# Control.net
KiCad netlist of a schematic drawn in Altium Designer
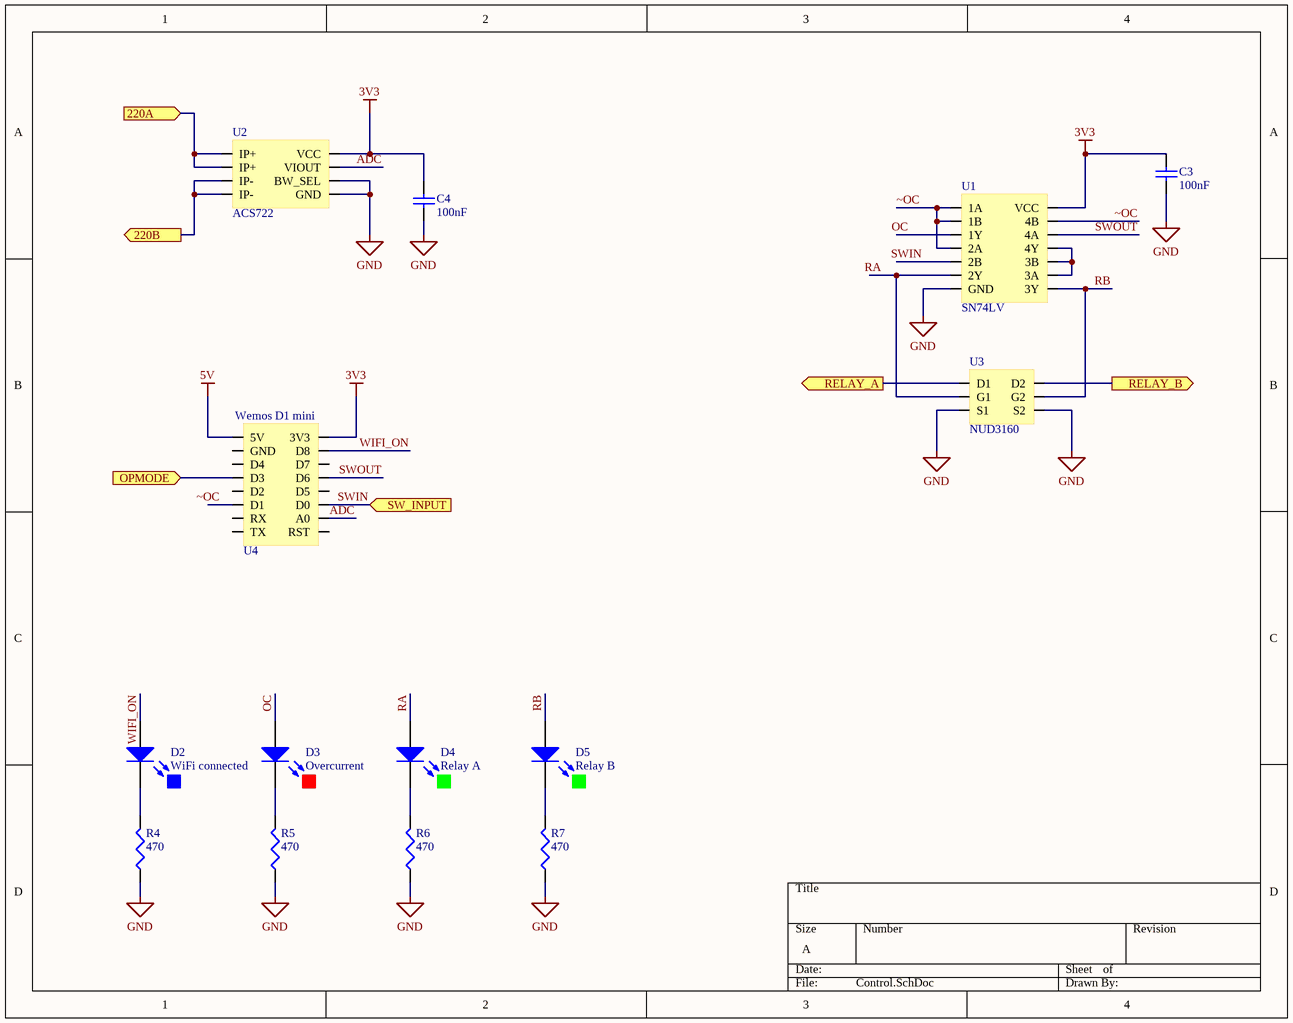
[diagram p0: Control.SchDoc]

(export (version "E")
  (design (tool "Eeschema 10.0.6"))
  (components
    (comp (ref "C3")
      (value "100nF")
      (footprint "C0805")
      (description "Capacitor")
      (fields
        (field (name "TOLERANCE") "80%")
        (field (name "VOLTAGE") "50V")
        (field (name "PUBLISHER") "Altium Limited")
      )
      (libsource (lib "Miscellaneous Devices") (part "Cap"))
    )
    (comp (ref "C4")
      (value "100nF")
      (footprint "C0805")
      (description "Capacitor")
      (fields
        (field (name "TOLERANCE") "80%")
        (field (name "VOLTAGE") "50V")
        (field (name "PUBLISHER") "Altium Limited")
      )
      (libsource (lib "Miscellaneous Devices") (part "Cap"))
    )
    (comp (ref "D2")
      (value "WiFi connected")
      (footprint "3.2X1.6X1.1")
      (description "Typical RED, GREEN, YELLOW, AMBER GaAs LED")
      (fields (field (name "PUBLISHER") "Altium Limited"))
      (libsource (lib "Miscellaneous Devices") (part "LED2"))
    )
    (comp (ref "D3")
      (value "Overcurrent")
      (footprint "3.2X1.6X1.1")
      (description "Typical RED, GREEN, YELLOW, AMBER GaAs LED")
      (fields (field (name "PUBLISHER") "Altium Limited"))
      (libsource (lib "Miscellaneous Devices") (part "LED2"))
    )
    (comp (ref "D4")
      (value "Relay A")
      (footprint "3.2X1.6X1.1")
      (description "Typical RED, GREEN, YELLOW, AMBER GaAs LED")
      (fields (field (name "PUBLISHER") "Altium Limited"))
      (libsource (lib "Miscellaneous Devices") (part "LED2"))
    )
    (comp (ref "D5")
      (value "Relay B")
      (footprint "3.2X1.6X1.1")
      (description "Typical RED, GREEN, YELLOW, AMBER GaAs LED")
      (fields (field (name "PUBLISHER") "Altium Limited"))
      (libsource (lib "Miscellaneous Devices") (part "LED2"))
    )
    (comp (ref "R4")
      (value "470")
      (footprint "J1-0603")
      (description "Resistor")
      (fields
        (field (name "TOLERANCE") "5%")
        (field (name "Comment") "Res3")
        (field (name "PUBLISHER") "Altium Limited")
      )
      (libsource (lib "Miscellaneous Devices") (part "Res3"))
    )
    (comp (ref "R5")
      (value "470")
      (footprint "J1-0603")
      (description "Resistor")
      (fields
        (field (name "TOLERANCE") "5%")
        (field (name "Comment") "Res3")
        (field (name "PUBLISHER") "Altium Limited")
      )
      (libsource (lib "Miscellaneous Devices") (part "Res3"))
    )
    (comp (ref "R6")
      (value "470")
      (footprint "J1-0603")
      (description "Resistor")
      (fields
        (field (name "TOLERANCE") "5%")
        (field (name "Comment") "Res3")
        (field (name "PUBLISHER") "Altium Limited")
      )
      (libsource (lib "Miscellaneous Devices") (part "Res3"))
    )
    (comp (ref "R7")
      (value "470")
      (footprint "J1-0603")
      (description "Resistor")
      (fields
        (field (name "TOLERANCE") "5%")
        (field (name "Comment") "Res3")
        (field (name "PUBLISHER") "Altium Limited")
      )
      (libsource (lib "Miscellaneous Devices") (part "Res3"))
    )
    (comp (ref "U1")
      (value "SN74LV")
      (footprint "TSSOP14")
      (description "IC GATE NAND 4CH 2-INP 14-SSOP")
      (libsource (lib "SmartplugComponents") (part "SN74LVC00APWR"))
    )
    (comp (ref "U2")
      (value "ACS722")
      (footprint "SOIC8")
      (description "SENSOR CURRENT HALL 20A AC/DC")
      (libsource (lib "SmartplugComponents") (part "ACS722LLCTR-20AB-T"))
    )
    (comp (ref "U3")
      (value "NUD3160")
      (footprint "SC-74")
      (description "IC INDCT LOAD DRVR INDUST SC74-6")
      (libsource (lib "SmartplugComponents") (part "NUD3160DMT1G"))
    )
    (comp (ref "U4")
      (value "Wemos D1 mini")
      (footprint "WEMOS_D1")
      (description "ESP8266 based MCU with Wi-Fi")
      (libsource (lib "SmartplugComponents") (part "ESP8266"))
    )
  )
  (nets
    (net (code "1") (name "/220A") (class "Default")
      (node (ref "U2") (pin "1") (pinfunction "IP+_1") (pintype "passive"))
      (node (ref "U2") (pin "2") (pinfunction "IP+_2") (pintype "passive"))
    )
    (net (code "2") (name "/220B") (class "Default")
      (node (ref "U2") (pin "3") (pinfunction "IP-_3") (pintype "passive"))
      (node (ref "U2") (pin "4") (pinfunction "IP-_4") (pintype "passive"))
    )
    (net (code "3") (name "/ADC") (class "Default")
      (node (ref "U2") (pin "7") (pinfunction "VIOUT_7") (pintype "passive"))
      (node (ref "U4") (pin "10") (pinfunction "A0_10") (pintype "passive"))
    )
    (net (code "4") (name "/OC") (class "Default")
      (node (ref "D3") (pin "1") (pinfunction "A_1") (pintype "passive"))
      (node (ref "U1") (pin "3") (pinfunction "1Y_3") (pintype "passive"))
    )
    (net (code "5") (name "/OPMODE") (class "Default")
      (node (ref "U4") (pin "4") (pinfunction "D3_4") (pintype "passive"))
    )
    (net (code "6") (name "/RA") (class "Default")
      (node (ref "D4") (pin "1") (pinfunction "A_1") (pintype "passive"))
      (node (ref "U1") (pin "6") (pinfunction "2Y_6") (pintype "passive"))
      (node (ref "U3") (pin "2") (pinfunction "G1_2") (pintype "passive"))
    )
    (net (code "7") (name "/RB") (class "Default")
      (node (ref "D5") (pin "1") (pinfunction "A_1") (pintype "passive"))
      (node (ref "U1") (pin "8") (pinfunction "3Y_8") (pintype "passive"))
      (node (ref "U3") (pin "5") (pinfunction "G2_5") (pintype "passive"))
    )
    (net (code "8") (name "/RELAY_A") (class "Default")
      (node (ref "U3") (pin "6") (pinfunction "D1_6") (pintype "passive"))
    )
    (net (code "9") (name "/RELAY_B") (class "Default")
      (node (ref "U3") (pin "3") (pinfunction "D2_3") (pintype "passive"))
    )
    (net (code "10") (name "/SWIN") (class "Default")
      (node (ref "U1") (pin "5") (pinfunction "2B_5") (pintype "passive"))
      (node (ref "U4") (pin "11") (pinfunction "D0_11") (pintype "passive"))
    )
    (net (code "11") (name "/SWOUT") (class "Default")
      (node (ref "U1") (pin "12") (pinfunction "4A_12") (pintype "passive"))
      (node (ref "U4") (pin "13") (pinfunction "D6_13") (pintype "passive"))
    )
    (net (code "12") (name "/WIFI_ON") (class "Default")
      (node (ref "D2") (pin "1") (pinfunction "A_1") (pintype "passive"))
      (node (ref "U4") (pin "15") (pinfunction "D8_15") (pintype "passive"))
    )
    (net (code "13") (name "/~OC") (class "Default")
      (node (ref "U1") (pin "1") (pinfunction "1A_1") (pintype "passive"))
      (node (ref "U1") (pin "13") (pinfunction "4B_13") (pintype "passive"))
      (node (ref "U1") (pin "2") (pinfunction "1B_2") (pintype "passive"))
      (node (ref "U1") (pin "4") (pinfunction "2A_4") (pintype "passive"))
      (node (ref "U4") (pin "6") (pinfunction "D1_6") (pintype "passive"))
    )
    (net (code "14") (name "3V3") (class "Default")
      (node (ref "C3") (pin "2") (pinfunction "2_2") (pintype "passive"))
      (node (ref "C4") (pin "2") (pinfunction "2_2") (pintype "passive"))
      (node (ref "U1") (pin "14") (pinfunction "VCC_14") (pintype "passive"))
      (node (ref "U2") (pin "8") (pinfunction "VCC_8") (pintype "passive"))
      (node (ref "U4") (pin "16") (pinfunction "3V3_16") (pintype "passive"))
    )
    (net (code "15") (name "5V") (class "Default")
      (node (ref "U4") (pin "1") (pinfunction "5V_1") (pintype "passive"))
    )
    (net (code "16") (name "GND") (class "Default")
      (node (ref "C3") (pin "1") (pinfunction "1_1") (pintype "passive"))
      (node (ref "C4") (pin "1") (pinfunction "1_1") (pintype "passive"))
      (node (ref "R4") (pin "1") (pinfunction "1_1") (pintype "passive"))
      (node (ref "R5") (pin "1") (pinfunction "1_1") (pintype "passive"))
      (node (ref "R6") (pin "1") (pinfunction "1_1") (pintype "passive"))
      (node (ref "R7") (pin "1") (pinfunction "1_1") (pintype "passive"))
      (node (ref "U1") (pin "7") (pinfunction "GND_7") (pintype "passive"))
      (node (ref "U2") (pin "5") (pinfunction "GND_5") (pintype "passive"))
      (node (ref "U2") (pin "6") (pinfunction "BW_SEL_6") (pintype "passive"))
      (node (ref "U3") (pin "1") (pinfunction "S1_1") (pintype "passive"))
      (node (ref "U3") (pin "4") (pinfunction "S2_4") (pintype "passive"))
    )
    (net (code "17") (name "Net-(D2-K)") (class "Default")
      (node (ref "D2") (pin "2") (pinfunction "K_2") (pintype "passive"))
      (node (ref "R4") (pin "2") (pinfunction "2_2") (pintype "passive"))
    )
    (net (code "18") (name "Net-(D3-K)") (class "Default")
      (node (ref "D3") (pin "2") (pinfunction "K_2") (pintype "passive"))
      (node (ref "R5") (pin "2") (pinfunction "2_2") (pintype "passive"))
    )
    (net (code "19") (name "Net-(D4-K)") (class "Default")
      (node (ref "D4") (pin "2") (pinfunction "K_2") (pintype "passive"))
      (node (ref "R6") (pin "2") (pinfunction "2_2") (pintype "passive"))
    )
    (net (code "20") (name "Net-(D5-K)") (class "Default")
      (node (ref "D5") (pin "2") (pinfunction "K_2") (pintype "passive"))
      (node (ref "R7") (pin "2") (pinfunction "2_2") (pintype "passive"))
    )
    (net (code "21") (name "Net-(U1-3A)") (class "Default")
      (node (ref "U1") (pin "10") (pinfunction "3B_10") (pintype "passive"))
      (node (ref "U1") (pin "11") (pinfunction "4Y_11") (pintype "passive"))
      (node (ref "U1") (pin "9") (pinfunction "3A_9") (pintype "passive"))
    )
    (net (code "22") (name "unconnected-(U4-D2-Pad5)") (class "Default")
      (node (ref "U4") (pin "5") (pinfunction "D2_5") (pintype "passive"))
    )
    (net (code "23") (name "unconnected-(U4-D4-Pad3)") (class "Default")
      (node (ref "U4") (pin "3") (pinfunction "D4_3") (pintype "passive"))
    )
    (net (code "24") (name "unconnected-(U4-D5-Pad12)") (class "Default")
      (node (ref "U4") (pin "12") (pinfunction "D5_12") (pintype "passive"))
    )
    (net (code "25") (name "unconnected-(U4-D7-Pad14)") (class "Default")
      (node (ref "U4") (pin "14") (pinfunction "D7_14") (pintype "passive"))
    )
    (net (code "26") (name "unconnected-(U4-GND-Pad2)") (class "Default")
      (node (ref "U4") (pin "2") (pinfunction "GND_2") (pintype "passive"))
    )
    (net (code "27") (name "unconnected-(U4-RST-Pad9)") (class "Default")
      (node (ref "U4") (pin "9") (pinfunction "RST_9") (pintype "passive"))
    )
    (net (code "28") (name "unconnected-(U4-RX-Pad7)") (class "Default")
      (node (ref "U4") (pin "7") (pinfunction "RX_7") (pintype "passive"))
    )
    (net (code "29") (name "unconnected-(U4-TX-Pad8)") (class "Default")
      (node (ref "U4") (pin "8") (pinfunction "TX_8") (pintype "passive"))
    )
  )
)
